# Radio.net
KiCad netlist of a schematic drawn in Altium Designer
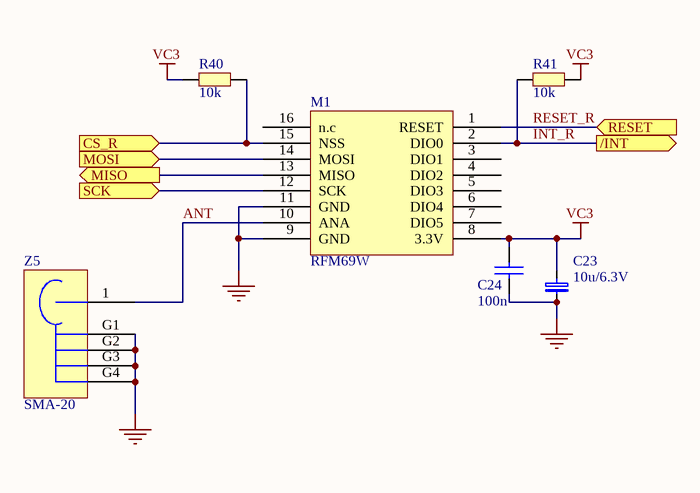
[diagram p0: Radio.SchDoc]

(export (version "E")
  (design (tool "Eeschema 10.0.6"))
  (components
    (comp (ref "C23")
      (value "10u/6.3V")
      (footprint "CAP_A")
      (description "KONDENSATOR ELEKTROLITYCZNY TANTALOWY SMD")
      (libsource (lib "*") (part "CAP_TANTAL_SMD"))
    )
    (comp (ref "C24")
      (value "100n")
      (footprint "0603C")
      (description "Capacitor")
      (libsource (lib "*") (part "CAP"))
    )
    (comp (ref "M1") (value "RFM69W") (footprint "RFM69W") (libsource (lib "GkSchlib") (part "RFM96W")))
    (comp (ref "R40") (value "10k") (footprint "0603R") (libsource (lib "*") (part "RES3")))
    (comp (ref "R41") (value "10k") (footprint "0603R") (libsource (lib "*") (part "RES3")))
    (comp (ref "Z5") (value "SMA-20") (footprint "SMA-20_1") (libsource (lib "*") (part "SMA-20")))
  )
  (nets
    (net (code "1") (name "/ANT") (class "Default")
      (node (ref "M1") (pin "10") (pinfunction "ANA_10") (pintype "passive"))
      (node (ref "Z5") (pin "1") (pintype "passive"))
    )
    (net (code "2") (name "/CS_R") (class "Default")
      (node (ref "M1") (pin "15") (pinfunction "NSS_15") (pintype "passive"))
      (node (ref "R40") (pin "1") (pintype "passive"))
    )
    (net (code "3") (name "/INT_R") (class "Default")
      (node (ref "M1") (pin "2") (pinfunction "DIO0_2") (pintype "passive"))
      (node (ref "R41") (pin "2") (pintype "passive"))
    )
    (net (code "4") (name "/MISO") (class "Default")
      (node (ref "M1") (pin "13") (pinfunction "MISO_13") (pintype "passive"))
    )
    (net (code "5") (name "/MOSI") (class "Default")
      (node (ref "M1") (pin "14") (pinfunction "MOSI_14") (pintype "passive"))
    )
    (net (code "6") (name "/RESET_R") (class "Default")
      (node (ref "M1") (pin "1") (pinfunction "RESET_1") (pintype "passive"))
    )
    (net (code "7") (name "/SCK") (class "Default")
      (node (ref "M1") (pin "12") (pinfunction "SCK_12") (pintype "passive"))
    )
    (net (code "8") (name "GND") (class "Default")
      (node (ref "C23") (pin "1") (pintype "passive"))
      (node (ref "C24") (pin "1") (pinfunction "1_1") (pintype "passive"))
      (node (ref "M1") (pin "11") (pinfunction "GND_11") (pintype "passive"))
      (node (ref "M1") (pin "9") (pinfunction "GND_9") (pintype "passive"))
      (node (ref "Z5") (pin "G1") (pintype "passive"))
      (node (ref "Z5") (pin "G2") (pintype "passive"))
      (node (ref "Z5") (pin "G3") (pintype "passive"))
      (node (ref "Z5") (pin "G4") (pintype "passive"))
    )
    (net (code "9") (name "VC3") (class "Default")
      (node (ref "C23") (pin "2") (pintype "passive"))
      (node (ref "C24") (pin "2") (pinfunction "2_2") (pintype "passive"))
      (node (ref "M1") (pin "8") (pinfunction "3.3V_8") (pintype "passive"))
      (node (ref "R40") (pin "2") (pintype "passive"))
      (node (ref "R41") (pin "1") (pintype "passive"))
    )
    (net (code "10") (name "unconnected-(M1-DIO1-Pad3)") (class "Default")
      (node (ref "M1") (pin "3") (pinfunction "DIO1_3") (pintype "passive"))
    )
    (net (code "11") (name "unconnected-(M1-DIO2-Pad4)") (class "Default")
      (node (ref "M1") (pin "4") (pinfunction "DIO2_4") (pintype "passive"))
    )
    (net (code "12") (name "unconnected-(M1-DIO3-Pad5)") (class "Default")
      (node (ref "M1") (pin "5") (pinfunction "DIO3_5") (pintype "passive"))
    )
    (net (code "13") (name "unconnected-(M1-DIO4-Pad6)") (class "Default")
      (node (ref "M1") (pin "6") (pinfunction "DIO4_6") (pintype "passive"))
    )
    (net (code "14") (name "unconnected-(M1-DIO5-Pad7)") (class "Default")
      (node (ref "M1") (pin "7") (pinfunction "DIO5_7") (pintype "passive"))
    )
    (net (code "15") (name "unconnected-(M1-n.c-Pad16)") (class "Default")
      (node (ref "M1") (pin "16") (pinfunction "n.c_16") (pintype "passive"))
    )
  )
)
